# EEU_PSSHI.net
KiCad netlist of a schematic drawn in Altium Designer
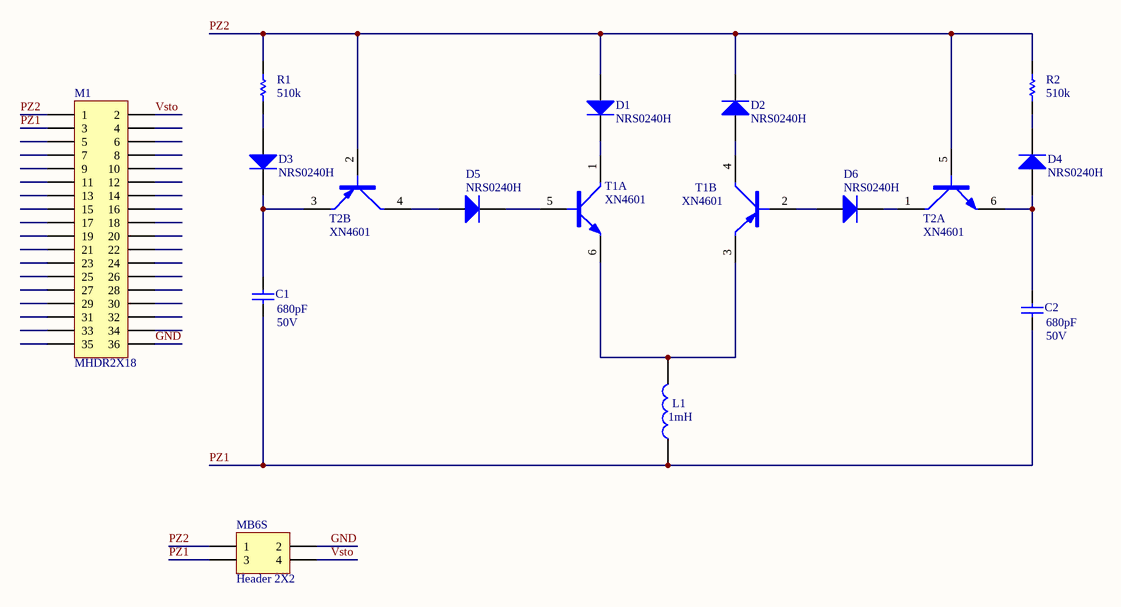
[diagram p0: EEU_PSSHI.SchDoc]

(export (version "E")
  (design (tool "Eeschema 10.0.6"))
  (components
    (comp (ref "C1")
      (value "680pF")
      (footprint "6-0805_N")
      (description "Capacitor")
      (fields
        (field (name "NOMINAL VOLTAGE") "50V")
        (field (name "Comment") "CAP")
        (field (name "PUBLISHER") "Altium Limited")
      )
      (libsource (lib "Harry_PCBLib") (part "Cap"))
    )
    (comp (ref "C2")
      (value "680pF")
      (footprint "6-0805_N")
      (description "Capacitor")
      (fields
        (field (name "NOMINAL VOLTAGE") "50V")
        (field (name "Comment") "CAP")
        (field (name "PUBLISHER") "Altium Limited")
      )
      (libsource (lib "Harry_PCBLib") (part "Cap"))
    )
    (comp (ref "D1")
      (value "NRS0240H")
      (footprint "SS16")
      (description "1 Amp General Purpose Rectifier")
      (fields (field (name "PUBLISHER") "Altium Limited"))
      (libsource (lib "Miscellaneous Devices") (part "Diode 1N4004"))
    )
    (comp (ref "D2")
      (value "NRS0240H")
      (footprint "SS16")
      (description "1 Amp General Purpose Rectifier")
      (fields (field (name "PUBLISHER") "Altium Limited"))
      (libsource (lib "Miscellaneous Devices") (part "Diode 1N4004"))
    )
    (comp (ref "D3")
      (value "NRS0240H")
      (footprint "SS16")
      (description "1 Amp General Purpose Rectifier")
      (fields (field (name "PUBLISHER") "Altium Limited"))
      (libsource (lib "Miscellaneous Devices") (part "Diode 1N4004"))
    )
    (comp (ref "D4")
      (value "NRS0240H")
      (footprint "SS16")
      (description "1 Amp General Purpose Rectifier")
      (fields (field (name "PUBLISHER") "Altium Limited"))
      (libsource (lib "Miscellaneous Devices") (part "Diode 1N4004"))
    )
    (comp (ref "D5")
      (value "NRS0240H")
      (footprint "SS16")
      (description "1 Amp General Purpose Rectifier")
      (fields (field (name "PUBLISHER") "Altium Limited"))
      (libsource (lib "Miscellaneous Devices") (part "Diode 1N4004"))
    )
    (comp (ref "D6")
      (value "NRS0240H")
      (footprint "SS16")
      (description "1 Amp General Purpose Rectifier")
      (fields (field (name "PUBLISHER") "Altium Limited"))
      (libsource (lib "Miscellaneous Devices") (part "Diode 1N4004"))
    )
    (comp (ref "L1") (value "1mH") (footprint "1812") (libsource (lib "Harry_PCBLib") (part "INDUCTOR")))
    (comp (ref "M1")
      (value "MHDR2X18")
      (footprint "module9x4")
      (description "Header, 18-Pin, Dual row")
      (fields (field (name "PUBLISHER") "Altium Limited"))
      (libsource (lib "Miscellaneous Connectors") (part "MHDR2X18"))
    )
    (comp (ref "MB6S")
      (value "Header 2X2")
      (footprint "MB6S")
      (description "Header, 2-Pin, Dual row")
      (fields (field (name "PUBLISHER") "Altium Limited"))
      (libsource (lib "Miscellaneous Connectors") (part "Header 2X2"))
    )
    (comp (ref "R1")
      (value "510k")
      (footprint "6-0805_N")
      (description "Resistor")
      (fields (field (name "Comment") "Res1") (field (name "PUBLISHER") "Altium Limited"))
      (libsource (lib "Miscellaneous Devices") (part "Res1"))
    )
    (comp (ref "R2")
      (value "510k")
      (footprint "6-0805_N")
      (description "Resistor")
      (fields (field (name "Comment") "Res1") (field (name "PUBLISHER") "Altium Limited"))
      (libsource (lib "Miscellaneous Devices") (part "Res1"))
    )
    (comp (ref "T1")
      (value "XN4601")
      (footprint "XN4601")
      (description "Composite Transistors")
      (libsource (lib "Self-power SSHI") (part "XN4601"))
    )
    (comp (ref "T2")
      (value "XN4601")
      (footprint "XN4601")
      (description "Composite Transistors")
      (libsource (lib "Self-power SSHI") (part "XN4601"))
    )
  )
  (nets
    (net (code "1") (name "/GND") (class "Default")
      (node (ref "M1") (pin "36") (pinfunction "36_36") (pintype "passive"))
      (node (ref "MB6S") (pin "2") (pinfunction "2_2") (pintype "passive"))
    )
    (net (code "2") (name "/PZ1") (class "Default")
      (node (ref "C1") (pin "1") (pinfunction "1_1") (pintype "passive"))
      (node (ref "C2") (pin "1") (pinfunction "1_1") (pintype "passive"))
      (node (ref "L1") (pin "1") (pinfunction "1_1") (pintype "passive"))
      (node (ref "M1") (pin "3") (pinfunction "3_3") (pintype "passive"))
      (node (ref "MB6S") (pin "3") (pinfunction "3_3") (pintype "passive"))
    )
    (net (code "3") (name "/PZ2") (class "Default")
      (node (ref "D1") (pin "1") (pinfunction "A_1") (pintype "passive"))
      (node (ref "D2") (pin "2") (pinfunction "K_2") (pintype "passive"))
      (node (ref "M1") (pin "1") (pinfunction "1_1") (pintype "passive"))
      (node (ref "MB6S") (pin "1") (pinfunction "1_1") (pintype "passive"))
      (node (ref "R1") (pin "2") (pinfunction "2_2") (pintype "passive"))
      (node (ref "R2") (pin "2") (pinfunction "2_2") (pintype "passive"))
      (node (ref "T2") (pin "2") (pinfunction "PNP_B_2") (pintype "passive"))
      (node (ref "T2") (pin "5") (pinfunction "NPN_B_5") (pintype "passive"))
    )
    (net (code "4") (name "/Vsto") (class "Default")
      (node (ref "M1") (pin "2") (pinfunction "2_2") (pintype "passive"))
      (node (ref "MB6S") (pin "4") (pinfunction "4_4") (pintype "passive"))
    )
    (net (code "5") (name "Net-(D1-K)") (class "Default")
      (node (ref "D1") (pin "2") (pinfunction "K_2") (pintype "passive"))
      (node (ref "T1") (pin "1") (pinfunction "NPN_C_1") (pintype "passive"))
    )
    (net (code "6") (name "Net-(D2-A)") (class "Default")
      (node (ref "D2") (pin "1") (pinfunction "A_1") (pintype "passive"))
      (node (ref "T1") (pin "4") (pinfunction "PNP_C_4") (pintype "passive"))
    )
    (net (code "7") (name "Net-(D3-A)") (class "Default")
      (node (ref "D3") (pin "1") (pinfunction "A_1") (pintype "passive"))
      (node (ref "R1") (pin "1") (pinfunction "1_1") (pintype "passive"))
    )
    (net (code "8") (name "Net-(D3-K)") (class "Default")
      (node (ref "C1") (pin "2") (pinfunction "2_2") (pintype "passive"))
      (node (ref "D3") (pin "2") (pinfunction "K_2") (pintype "passive"))
      (node (ref "T2") (pin "3") (pinfunction "PNP_E_3") (pintype "passive"))
    )
    (net (code "9") (name "Net-(D4-A)") (class "Default")
      (node (ref "C2") (pin "2") (pinfunction "2_2") (pintype "passive"))
      (node (ref "D4") (pin "1") (pinfunction "A_1") (pintype "passive"))
      (node (ref "T2") (pin "6") (pinfunction "NPN_E_6") (pintype "passive"))
    )
    (net (code "10") (name "Net-(D4-K)") (class "Default")
      (node (ref "D4") (pin "2") (pinfunction "K_2") (pintype "passive"))
      (node (ref "R2") (pin "1") (pinfunction "1_1") (pintype "passive"))
    )
    (net (code "11") (name "Net-(D5-A)") (class "Default")
      (node (ref "D5") (pin "1") (pinfunction "A_1") (pintype "passive"))
      (node (ref "T2") (pin "4") (pinfunction "PNP_C_4") (pintype "passive"))
    )
    (net (code "12") (name "Net-(D5-K)") (class "Default")
      (node (ref "D5") (pin "2") (pinfunction "K_2") (pintype "passive"))
      (node (ref "T1") (pin "5") (pinfunction "NPN_B_5") (pintype "passive"))
    )
    (net (code "13") (name "Net-(D6-A)") (class "Default")
      (node (ref "D6") (pin "1") (pinfunction "A_1") (pintype "passive"))
      (node (ref "T1") (pin "2") (pinfunction "PNP_B_2") (pintype "passive"))
    )
    (net (code "14") (name "Net-(D6-K)") (class "Default")
      (node (ref "D6") (pin "2") (pinfunction "K_2") (pintype "passive"))
      (node (ref "T2") (pin "1") (pinfunction "NPN_C_1") (pintype "passive"))
    )
    (net (code "15") (name "Net-(T1A-NPN_E)") (class "Default")
      (node (ref "L1") (pin "2") (pinfunction "2_2") (pintype "passive"))
      (node (ref "T1") (pin "3") (pinfunction "PNP_E_3") (pintype "passive"))
      (node (ref "T1") (pin "6") (pinfunction "NPN_E_6") (pintype "passive"))
    )
    (net (code "16") (name "unconnected-(M1-Pad4)") (class "Default")
      (node (ref "M1") (pin "4") (pinfunction "4_4") (pintype "passive"))
    )
    (net (code "17") (name "unconnected-(M1-Pad5)") (class "Default")
      (node (ref "M1") (pin "5") (pinfunction "5_5") (pintype "passive"))
    )
    (net (code "18") (name "unconnected-(M1-Pad6)") (class "Default")
      (node (ref "M1") (pin "6") (pinfunction "6_6") (pintype "passive"))
    )
    (net (code "19") (name "unconnected-(M1-Pad7)") (class "Default")
      (node (ref "M1") (pin "7") (pinfunction "7_7") (pintype "passive"))
    )
    (net (code "20") (name "unconnected-(M1-Pad8)") (class "Default")
      (node (ref "M1") (pin "8") (pinfunction "8_8") (pintype "passive"))
    )
    (net (code "21") (name "unconnected-(M1-Pad9)") (class "Default")
      (node (ref "M1") (pin "9") (pinfunction "9_9") (pintype "passive"))
    )
    (net (code "22") (name "unconnected-(M1-Pad10)") (class "Default")
      (node (ref "M1") (pin "10") (pinfunction "10_10") (pintype "passive"))
    )
    (net (code "23") (name "unconnected-(M1-Pad11)") (class "Default")
      (node (ref "M1") (pin "11") (pinfunction "11_11") (pintype "passive"))
    )
    (net (code "24") (name "unconnected-(M1-Pad12)") (class "Default")
      (node (ref "M1") (pin "12") (pinfunction "12_12") (pintype "passive"))
    )
    (net (code "25") (name "unconnected-(M1-Pad13)") (class "Default")
      (node (ref "M1") (pin "13") (pinfunction "13_13") (pintype "passive"))
    )
    (net (code "26") (name "unconnected-(M1-Pad14)") (class "Default")
      (node (ref "M1") (pin "14") (pinfunction "14_14") (pintype "passive"))
    )
    (net (code "27") (name "unconnected-(M1-Pad15)") (class "Default")
      (node (ref "M1") (pin "15") (pinfunction "15_15") (pintype "passive"))
    )
    (net (code "28") (name "unconnected-(M1-Pad16)") (class "Default")
      (node (ref "M1") (pin "16") (pinfunction "16_16") (pintype "passive"))
    )
    (net (code "29") (name "unconnected-(M1-Pad17)") (class "Default")
      (node (ref "M1") (pin "17") (pinfunction "17_17") (pintype "passive"))
    )
    (net (code "30") (name "unconnected-(M1-Pad18)") (class "Default")
      (node (ref "M1") (pin "18") (pinfunction "18_18") (pintype "passive"))
    )
    (net (code "31") (name "unconnected-(M1-Pad19)") (class "Default")
      (node (ref "M1") (pin "19") (pinfunction "19_19") (pintype "passive"))
    )
    (net (code "32") (name "unconnected-(M1-Pad20)") (class "Default")
      (node (ref "M1") (pin "20") (pinfunction "20_20") (pintype "passive"))
    )
    (net (code "33") (name "unconnected-(M1-Pad21)") (class "Default")
      (node (ref "M1") (pin "21") (pinfunction "21_21") (pintype "passive"))
    )
    (net (code "34") (name "unconnected-(M1-Pad22)") (class "Default")
      (node (ref "M1") (pin "22") (pinfunction "22_22") (pintype "passive"))
    )
    (net (code "35") (name "unconnected-(M1-Pad23)") (class "Default")
      (node (ref "M1") (pin "23") (pinfunction "23_23") (pintype "passive"))
    )
    (net (code "36") (name "unconnected-(M1-Pad24)") (class "Default")
      (node (ref "M1") (pin "24") (pinfunction "24_24") (pintype "passive"))
    )
    (net (code "37") (name "unconnected-(M1-Pad25)") (class "Default")
      (node (ref "M1") (pin "25") (pinfunction "25_25") (pintype "passive"))
    )
    (net (code "38") (name "unconnected-(M1-Pad26)") (class "Default")
      (node (ref "M1") (pin "26") (pinfunction "26_26") (pintype "passive"))
    )
    (net (code "39") (name "unconnected-(M1-Pad27)") (class "Default")
      (node (ref "M1") (pin "27") (pinfunction "27_27") (pintype "passive"))
    )
    (net (code "40") (name "unconnected-(M1-Pad28)") (class "Default")
      (node (ref "M1") (pin "28") (pinfunction "28_28") (pintype "passive"))
    )
    (net (code "41") (name "unconnected-(M1-Pad29)") (class "Default")
      (node (ref "M1") (pin "29") (pinfunction "29_29") (pintype "passive"))
    )
    (net (code "42") (name "unconnected-(M1-Pad30)") (class "Default")
      (node (ref "M1") (pin "30") (pinfunction "30_30") (pintype "passive"))
    )
    (net (code "43") (name "unconnected-(M1-Pad31)") (class "Default")
      (node (ref "M1") (pin "31") (pinfunction "31_31") (pintype "passive"))
    )
    (net (code "44") (name "unconnected-(M1-Pad32)") (class "Default")
      (node (ref "M1") (pin "32") (pinfunction "32_32") (pintype "passive"))
    )
    (net (code "45") (name "unconnected-(M1-Pad33)") (class "Default")
      (node (ref "M1") (pin "33") (pinfunction "33_33") (pintype "passive"))
    )
    (net (code "46") (name "unconnected-(M1-Pad34)") (class "Default")
      (node (ref "M1") (pin "34") (pinfunction "34_34") (pintype "passive"))
    )
    (net (code "47") (name "unconnected-(M1-Pad35)") (class "Default")
      (node (ref "M1") (pin "35") (pinfunction "35_35") (pintype "passive"))
    )
  )
)
